# FPGA_power_v3.net
KiCad netlist of a schematic drawn in Altium Designer
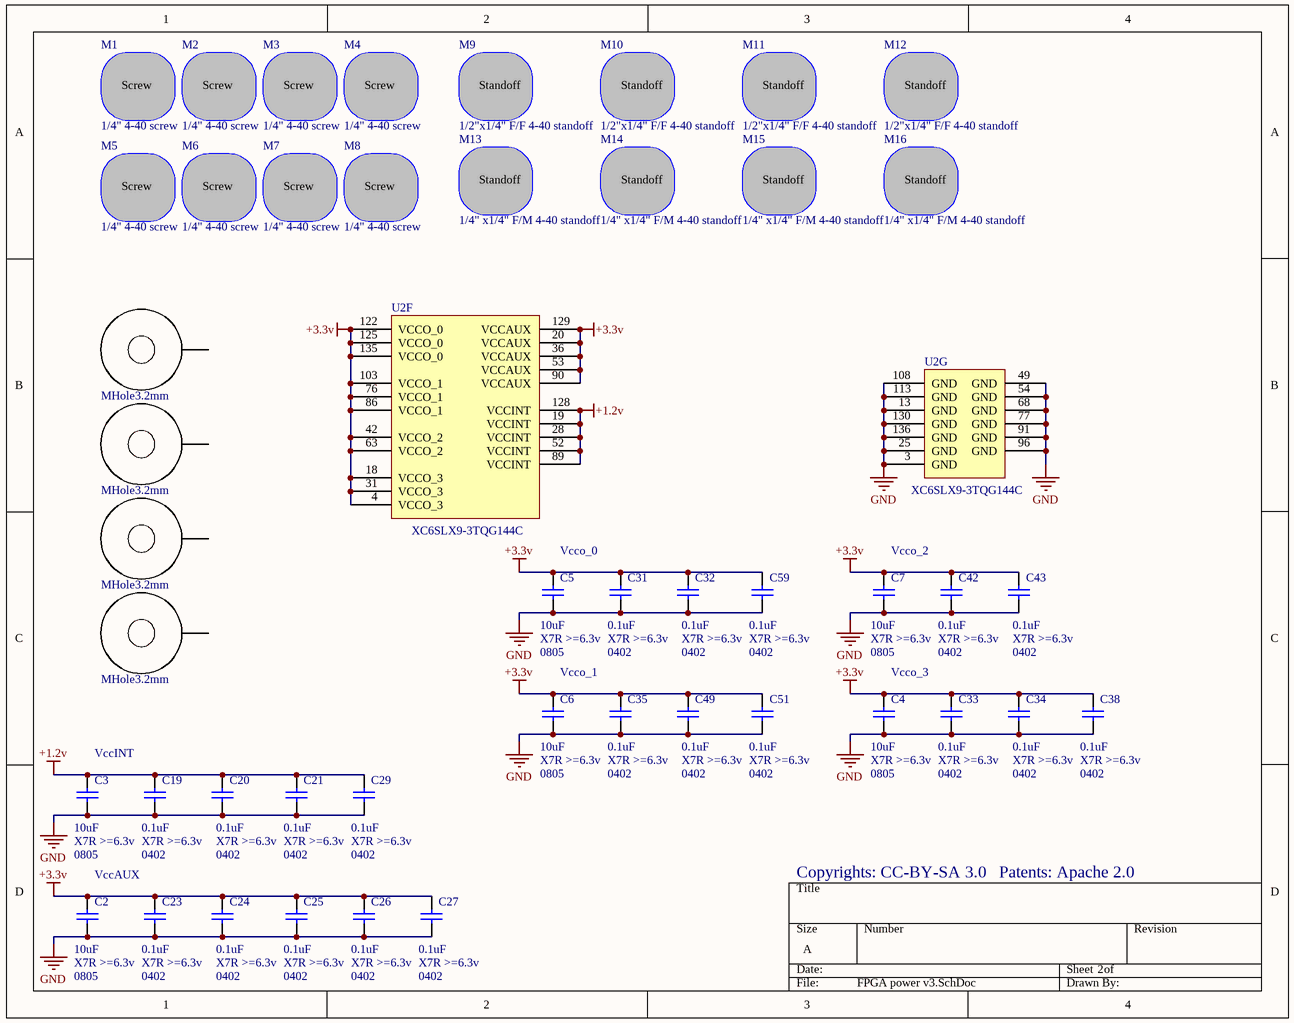
[diagram p0: FPGA power v3.SchDoc]

(export (version "E")
  (design (tool "Eeschema 10.0.6"))
  (components
    (comp (ref "C2")
      (value "10uF")
      (footprint "CAPC2012N")
      (description "CAP CER 0.1UF 25V 10% X5R 0603")
      (fields
        (field (name "PACKAGEREFERENCE") "0805")
        (field (name "TOLERANCE") "±10%")
        (field (name "RATING") "X7R >=6.3v")
      )
      (libsource (lib "Miscellaneous Devices") (part "Cap Semi"))
    )
    (comp (ref "C3")
      (value "10uF")
      (footprint "CAPC2012N")
      (description "CAP CER 0.1UF 25V 10% X5R 0603")
      (fields
        (field (name "PACKAGEREFERENCE") "0805")
        (field (name "TOLERANCE") "±10%")
        (field (name "RATING") "X7R >=6.3v")
      )
      (libsource (lib "Miscellaneous Devices") (part "Cap Semi"))
    )
    (comp (ref "C4")
      (value "10uF")
      (footprint "CAPC2012N")
      (description "CAP CER 0.1UF 25V 10% X5R 0603")
      (fields
        (field (name "PACKAGEREFERENCE") "0805")
        (field (name "TOLERANCE") "±10%")
        (field (name "RATING") "X7R >=6.3v")
      )
      (libsource (lib "Miscellaneous Devices") (part "Cap Semi"))
    )
    (comp (ref "C5")
      (value "10uF")
      (footprint "CAPC2012N")
      (description "CAP CER 0.1UF 25V 10% X5R 0603")
      (fields
        (field (name "PACKAGEREFERENCE") "0805")
        (field (name "TOLERANCE") "±10%")
        (field (name "RATING") "X7R >=6.3v")
      )
      (libsource (lib "Miscellaneous Devices") (part "Cap Semi"))
    )
    (comp (ref "C6")
      (value "10uF")
      (footprint "CAPC2012N")
      (description "CAP CER 0.1UF 25V 10% X5R 0603")
      (fields
        (field (name "PACKAGEREFERENCE") "0805")
        (field (name "TOLERANCE") "±10%")
        (field (name "RATING") "X7R >=6.3v")
      )
      (libsource (lib "Miscellaneous Devices") (part "Cap Semi"))
    )
    (comp (ref "C7")
      (value "10uF")
      (footprint "CAPC2012N")
      (description "CAP CER 0.1UF 25V 10% X5R 0603")
      (fields
        (field (name "PACKAGEREFERENCE") "0805")
        (field (name "TOLERANCE") "±10%")
        (field (name "RATING") "X7R >=6.3v")
      )
      (libsource (lib "Miscellaneous Devices") (part "Cap Semi"))
    )
    (comp (ref "C19")
      (value "0.1uF")
      (footprint "CAPC1005N")
      (description "CAP CER 0.1UF 25V 10% X5R 0603")
      (fields
        (field (name "PACKAGEREFERENCE") "0402")
        (field (name "TOLERANCE") "±10%")
        (field (name "RATING") "X7R >=6.3v")
      )
      (libsource (lib "Miscellaneous Devices") (part "Cap Semi"))
    )
    (comp (ref "C20")
      (value "0.1uF")
      (footprint "CAPC1005N")
      (description "CAP CER 0.1UF 25V 10% X5R 0603")
      (fields
        (field (name "PACKAGEREFERENCE") "0402")
        (field (name "TOLERANCE") "±10%")
        (field (name "RATING") "X7R >=6.3v")
      )
      (libsource (lib "Miscellaneous Devices") (part "Cap Semi"))
    )
    (comp (ref "C21")
      (value "0.1uF")
      (footprint "CAPC1005N")
      (description "CAP CER 0.1UF 25V 10% X5R 0603")
      (fields
        (field (name "PACKAGEREFERENCE") "0402")
        (field (name "TOLERANCE") "±10%")
        (field (name "RATING") "X7R >=6.3v")
      )
      (libsource (lib "Miscellaneous Devices") (part "Cap Semi"))
    )
    (comp (ref "C23")
      (value "0.1uF")
      (footprint "CAPC1005N")
      (description "CAP CER 0.1UF 25V 10% X5R 0603")
      (fields
        (field (name "PACKAGEREFERENCE") "0402")
        (field (name "TOLERANCE") "±10%")
        (field (name "RATING") "X7R >=6.3v")
      )
      (libsource (lib "Miscellaneous Devices") (part "Cap Semi"))
    )
    (comp (ref "C24")
      (value "0.1uF")
      (footprint "CAPC1005N")
      (description "CAP CER 0.1UF 25V 10% X5R 0603")
      (fields
        (field (name "PACKAGEREFERENCE") "0402")
        (field (name "TOLERANCE") "±10%")
        (field (name "RATING") "X7R >=6.3v")
      )
      (libsource (lib "Miscellaneous Devices") (part "Cap Semi"))
    )
    (comp (ref "C25")
      (value "0.1uF")
      (footprint "CAPC1005N")
      (description "CAP CER 0.1UF 25V 10% X5R 0603")
      (fields
        (field (name "PACKAGEREFERENCE") "0402")
        (field (name "TOLERANCE") "±10%")
        (field (name "RATING") "X7R >=6.3v")
      )
      (libsource (lib "Miscellaneous Devices") (part "Cap Semi"))
    )
    (comp (ref "C26")
      (value "0.1uF")
      (footprint "CAPC1005N")
      (description "CAP CER 0.1UF 25V 10% X5R 0603")
      (fields
        (field (name "PACKAGEREFERENCE") "0402")
        (field (name "TOLERANCE") "±10%")
        (field (name "RATING") "X7R >=6.3v")
      )
      (libsource (lib "Miscellaneous Devices") (part "Cap Semi"))
    )
    (comp (ref "C27")
      (value "0.1uF")
      (footprint "CAPC1005N")
      (description "CAP CER 0.1UF 25V 10% X5R 0603")
      (fields
        (field (name "PACKAGEREFERENCE") "0402")
        (field (name "TOLERANCE") "±10%")
        (field (name "RATING") "X7R >=6.3v")
      )
      (libsource (lib "Miscellaneous Devices") (part "Cap Semi"))
    )
    (comp (ref "C29")
      (value "0.1uF")
      (footprint "CAPC1005N")
      (description "CAP CER 0.1UF 25V 10% X5R 0603")
      (fields
        (field (name "PACKAGEREFERENCE") "0402")
        (field (name "TOLERANCE") "±10%")
        (field (name "RATING") "X7R >=6.3v")
      )
      (libsource (lib "Miscellaneous Devices") (part "Cap Semi"))
    )
    (comp (ref "C31")
      (value "0.1uF")
      (footprint "CAPC1005N")
      (description "CAP CER 0.1UF 25V 10% X5R 0603")
      (fields
        (field (name "PACKAGEREFERENCE") "0402")
        (field (name "TOLERANCE") "±10%")
        (field (name "RATING") "X7R >=6.3v")
      )
      (libsource (lib "Miscellaneous Devices") (part "Cap Semi"))
    )
    (comp (ref "C32")
      (value "0.1uF")
      (footprint "CAPC1005N")
      (description "CAP CER 0.1UF 25V 10% X5R 0603")
      (fields
        (field (name "PACKAGEREFERENCE") "0402")
        (field (name "TOLERANCE") "±10%")
        (field (name "RATING") "X7R >=6.3v")
      )
      (libsource (lib "Miscellaneous Devices") (part "Cap Semi"))
    )
    (comp (ref "C33")
      (value "0.1uF")
      (footprint "CAPC1005N")
      (description "CAP CER 0.1UF 25V 10% X5R 0603")
      (fields
        (field (name "PACKAGEREFERENCE") "0402")
        (field (name "TOLERANCE") "±10%")
        (field (name "RATING") "X7R >=6.3v")
      )
      (libsource (lib "Miscellaneous Devices") (part "Cap Semi"))
    )
    (comp (ref "C34")
      (value "0.1uF")
      (footprint "CAPC1005N")
      (description "CAP CER 0.1UF 25V 10% X5R 0603")
      (fields
        (field (name "PACKAGEREFERENCE") "0402")
        (field (name "TOLERANCE") "±10%")
        (field (name "RATING") "X7R >=6.3v")
      )
      (libsource (lib "Miscellaneous Devices") (part "Cap Semi"))
    )
    (comp (ref "C35")
      (value "0.1uF")
      (footprint "CAPC1005N")
      (description "CAP CER 0.1UF 25V 10% X5R 0603")
      (fields
        (field (name "PACKAGEREFERENCE") "0402")
        (field (name "TOLERANCE") "±10%")
        (field (name "RATING") "X7R >=6.3v")
      )
      (libsource (lib "Miscellaneous Devices") (part "Cap Semi"))
    )
    (comp (ref "C38")
      (value "0.1uF")
      (footprint "CAPC1005N")
      (description "CAP CER 0.1UF 25V 10% X5R 0603")
      (fields
        (field (name "PACKAGEREFERENCE") "0402")
        (field (name "TOLERANCE") "±10%")
        (field (name "RATING") "X7R >=6.3v")
      )
      (libsource (lib "Miscellaneous Devices") (part "Cap Semi"))
    )
    (comp (ref "C42")
      (value "0.1uF")
      (footprint "CAPC1005N")
      (description "CAP CER 0.1UF 25V 10% X5R 0603")
      (fields
        (field (name "PACKAGEREFERENCE") "0402")
        (field (name "TOLERANCE") "±10%")
        (field (name "RATING") "X7R >=6.3v")
      )
      (libsource (lib "Miscellaneous Devices") (part "Cap Semi"))
    )
    (comp (ref "C43")
      (value "0.1uF")
      (footprint "CAPC1005N")
      (description "CAP CER 0.1UF 25V 10% X5R 0603")
      (fields
        (field (name "PACKAGEREFERENCE") "0402")
        (field (name "TOLERANCE") "±10%")
        (field (name "RATING") "X7R >=6.3v")
      )
      (libsource (lib "Miscellaneous Devices") (part "Cap Semi"))
    )
    (comp (ref "C49")
      (value "0.1uF")
      (footprint "CAPC1005N")
      (description "CAP CER 0.1UF 25V 10% X5R 0603")
      (fields
        (field (name "PACKAGEREFERENCE") "0402")
        (field (name "TOLERANCE") "±10%")
        (field (name "RATING") "X7R >=6.3v")
      )
      (libsource (lib "Miscellaneous Devices") (part "Cap Semi"))
    )
    (comp (ref "C51")
      (value "0.1uF")
      (footprint "CAPC1005N")
      (description "CAP CER 0.1UF 25V 10% X5R 0603")
      (fields
        (field (name "PACKAGEREFERENCE") "0402")
        (field (name "TOLERANCE") "±10%")
        (field (name "RATING") "X7R >=6.3v")
      )
      (libsource (lib "Miscellaneous Devices") (part "Cap Semi"))
    )
    (comp (ref "C59")
      (value "0.1uF")
      (footprint "CAPC1005N")
      (description "CAP CER 0.1UF 25V 10% X5R 0603")
      (fields
        (field (name "PACKAGEREFERENCE") "0402")
        (field (name "TOLERANCE") "±10%")
        (field (name "RATING") "X7R >=6.3v")
      )
      (libsource (lib "Miscellaneous Devices") (part "Cap Semi"))
    )
    (comp (ref "H1") (value "MHole3.2mm") (footprint "mounting hole") (libsource (lib "dbww") (part "MHole")))
    (comp (ref "H2") (value "MHole3.2mm") (footprint "mounting hole") (libsource (lib "dbww") (part "MHole")))
    (comp (ref "H3") (value "MHole3.2mm") (footprint "mounting hole") (libsource (lib "dbww") (part "MHole")))
    (comp (ref "H4") (value "MHole3.2mm") (footprint "mounting hole") (libsource (lib "dbww") (part "MHole")))
    (comp (ref "M1")
      (value "1/4\" 4-40 screw")
      (footprint "fiducial")
      (libsource (lib "OpenVizsla symbols") (part "Screw"))
    )
    (comp (ref "M2")
      (value "1/4\" 4-40 screw")
      (footprint "fiducial")
      (libsource (lib "OpenVizsla symbols") (part "Screw"))
    )
    (comp (ref "M3")
      (value "1/4\" 4-40 screw")
      (footprint "fiducial")
      (libsource (lib "OpenVizsla symbols") (part "Screw"))
    )
    (comp (ref "M4")
      (value "1/4\" 4-40 screw")
      (footprint "fiducial")
      (libsource (lib "OpenVizsla symbols") (part "Screw"))
    )
    (comp (ref "M5")
      (value "1/4\" 4-40 screw")
      (footprint "fiducial")
      (libsource (lib "OpenVizsla symbols") (part "Screw"))
    )
    (comp (ref "M6")
      (value "1/4\" 4-40 screw")
      (footprint "fiducial")
      (libsource (lib "OpenVizsla symbols") (part "Screw"))
    )
    (comp (ref "M7")
      (value "1/4\" 4-40 screw")
      (footprint "fiducial")
      (libsource (lib "OpenVizsla symbols") (part "Screw"))
    )
    (comp (ref "M8")
      (value "1/4\" 4-40 screw")
      (footprint "fiducial")
      (libsource (lib "OpenVizsla symbols") (part "Screw"))
    )
    (comp (ref "M9")
      (value "1/2\"x1/4\" F/F 4-40 standoff")
      (footprint "fiducial")
      (libsource (lib "OpenVizsla symbols") (part "Standoff"))
    )
    (comp (ref "M10")
      (value "1/2\"x1/4\" F/F 4-40 standoff")
      (footprint "fiducial")
      (libsource (lib "OpenVizsla symbols") (part "Standoff"))
    )
    (comp (ref "M11")
      (value "1/2\"x1/4\" F/F 4-40 standoff")
      (footprint "fiducial")
      (libsource (lib "OpenVizsla symbols") (part "Standoff"))
    )
    (comp (ref "M12")
      (value "1/2\"x1/4\" F/F 4-40 standoff")
      (footprint "fiducial")
      (libsource (lib "OpenVizsla symbols") (part "Standoff"))
    )
    (comp (ref "M13")
      (value "1/4\" x1/4\" F/M 4-40 standoff")
      (footprint "fiducial")
      (description "1/4\"x1/4\" F/M 4-40 standof")
      (libsource (lib "OpenVizsla symbols") (part "Standoff"))
    )
    (comp (ref "M14")
      (value "1/4\" x1/4\" F/M 4-40 standoff")
      (footprint "fiducial")
      (description "1/4\"x1/4\" F/M 4-40 standof")
      (libsource (lib "OpenVizsla symbols") (part "Standoff"))
    )
    (comp (ref "M15")
      (value "1/4\" x1/4\" F/M 4-40 standoff")
      (footprint "fiducial")
      (description "1/4\"x1/4\" F/M 4-40 standof")
      (libsource (lib "OpenVizsla symbols") (part "Standoff"))
    )
    (comp (ref "M16")
      (value "1/4\" x1/4\" F/M 4-40 standoff")
      (footprint "fiducial")
      (description "1/4\"x1/4\" F/M 4-40 standof")
      (libsource (lib "OpenVizsla symbols") (part "Standoff"))
    )
    (comp (ref "U2")
      (value "XC6SLX9-3TQG144C")
      (footprint "TQG144_N")
      (libsource (lib "Xilinx Spartan-6") (part "XC6SLX9-3TQG144C"))
    )
  )
  (nets
    (net (code "1") (name "+1.2v") (class "Default")
      (node (ref "C19") (pin "2") (pinfunction "2_2") (pintype "passive"))
      (node (ref "C20") (pin "2") (pinfunction "2_2") (pintype "passive"))
      (node (ref "C21") (pin "2") (pinfunction "2_2") (pintype "passive"))
      (node (ref "C29") (pin "2") (pinfunction "2_2") (pintype "passive"))
      (node (ref "C3") (pin "2") (pinfunction "2_2") (pintype "passive"))
      (node (ref "U2") (pin "128") (pinfunction "VCCINT_128") (pintype "power_in"))
      (node (ref "U2") (pin "19") (pinfunction "VCCINT_19") (pintype "power_in"))
      (node (ref "U2") (pin "28") (pinfunction "VCCINT_28") (pintype "power_in"))
      (node (ref "U2") (pin "52") (pinfunction "VCCINT_52") (pintype "power_in"))
      (node (ref "U2") (pin "89") (pinfunction "VCCINT_89") (pintype "power_in"))
    )
    (net (code "2") (name "+3.3v") (class "Default")
      (node (ref "C2") (pin "2") (pinfunction "2_2") (pintype "passive"))
      (node (ref "C23") (pin "2") (pinfunction "2_2") (pintype "passive"))
      (node (ref "C24") (pin "2") (pinfunction "2_2") (pintype "passive"))
      (node (ref "C25") (pin "2") (pinfunction "2_2") (pintype "passive"))
      (node (ref "C26") (pin "2") (pinfunction "2_2") (pintype "passive"))
      (node (ref "C27") (pin "2") (pinfunction "2_2") (pintype "passive"))
      (node (ref "C31") (pin "2") (pinfunction "2_2") (pintype "passive"))
      (node (ref "C32") (pin "2") (pinfunction "2_2") (pintype "passive"))
      (node (ref "C33") (pin "2") (pinfunction "2_2") (pintype "passive"))
      (node (ref "C34") (pin "2") (pinfunction "2_2") (pintype "passive"))
      (node (ref "C35") (pin "2") (pinfunction "2_2") (pintype "passive"))
      (node (ref "C38") (pin "2") (pinfunction "2_2") (pintype "passive"))
      (node (ref "C4") (pin "2") (pinfunction "2_2") (pintype "passive"))
      (node (ref "C42") (pin "2") (pinfunction "2_2") (pintype "passive"))
      (node (ref "C43") (pin "2") (pinfunction "2_2") (pintype "passive"))
      (node (ref "C49") (pin "2") (pinfunction "2_2") (pintype "passive"))
      (node (ref "C5") (pin "2") (pinfunction "2_2") (pintype "passive"))
      (node (ref "C51") (pin "2") (pinfunction "2_2") (pintype "passive"))
      (node (ref "C59") (pin "2") (pinfunction "2_2") (pintype "passive"))
      (node (ref "C6") (pin "2") (pinfunction "2_2") (pintype "passive"))
      (node (ref "C7") (pin "2") (pinfunction "2_2") (pintype "passive"))
      (node (ref "U2") (pin "103") (pinfunction "VCCO_1_103") (pintype "power_in"))
      (node (ref "U2") (pin "122") (pinfunction "VCCO_0_122") (pintype "power_in"))
      (node (ref "U2") (pin "125") (pinfunction "VCCO_0_125") (pintype "power_in"))
      (node (ref "U2") (pin "129") (pinfunction "VCCAUX_129") (pintype "power_in"))
      (node (ref "U2") (pin "135") (pinfunction "VCCO_0_135") (pintype "power_in"))
      (node (ref "U2") (pin "18") (pinfunction "VCCO_3_18") (pintype "power_in"))
      (node (ref "U2") (pin "20") (pinfunction "VCCAUX_20") (pintype "power_in"))
      (node (ref "U2") (pin "31") (pinfunction "VCCO_3_31") (pintype "power_in"))
      (node (ref "U2") (pin "36") (pinfunction "VCCAUX_36") (pintype "power_in"))
      (node (ref "U2") (pin "4") (pinfunction "VCCO_3_4") (pintype "power_in"))
      (node (ref "U2") (pin "42") (pinfunction "VCCO_2_42") (pintype "power_in"))
      (node (ref "U2") (pin "53") (pinfunction "VCCAUX_53") (pintype "power_in"))
      (node (ref "U2") (pin "63") (pinfunction "VCCO_2_63") (pintype "power_in"))
      (node (ref "U2") (pin "76") (pinfunction "VCCO_1_76") (pintype "power_in"))
      (node (ref "U2") (pin "86") (pinfunction "VCCO_1_86") (pintype "power_in"))
      (node (ref "U2") (pin "90") (pinfunction "VCCAUX_90") (pintype "power_in"))
    )
    (net (code "3") (name "GND") (class "Default")
      (node (ref "C19") (pin "1") (pinfunction "1_1") (pintype "passive"))
      (node (ref "C2") (pin "1") (pinfunction "1_1") (pintype "passive"))
      (node (ref "C20") (pin "1") (pinfunction "1_1") (pintype "passive"))
      (node (ref "C21") (pin "1") (pinfunction "1_1") (pintype "passive"))
      (node (ref "C23") (pin "1") (pinfunction "1_1") (pintype "passive"))
      (node (ref "C24") (pin "1") (pinfunction "1_1") (pintype "passive"))
      (node (ref "C25") (pin "1") (pinfunction "1_1") (pintype "passive"))
      (node (ref "C26") (pin "1") (pinfunction "1_1") (pintype "passive"))
      (node (ref "C27") (pin "1") (pinfunction "1_1") (pintype "passive"))
      (node (ref "C29") (pin "1") (pinfunction "1_1") (pintype "passive"))
      (node (ref "C3") (pin "1") (pinfunction "1_1") (pintype "passive"))
      (node (ref "C31") (pin "1") (pinfunction "1_1") (pintype "passive"))
      (node (ref "C32") (pin "1") (pinfunction "1_1") (pintype "passive"))
      (node (ref "C33") (pin "1") (pinfunction "1_1") (pintype "passive"))
      (node (ref "C34") (pin "1") (pinfunction "1_1") (pintype "passive"))
      (node (ref "C35") (pin "1") (pinfunction "1_1") (pintype "passive"))
      (node (ref "C38") (pin "1") (pinfunction "1_1") (pintype "passive"))
      (node (ref "C4") (pin "1") (pinfunction "1_1") (pintype "passive"))
      (node (ref "C42") (pin "1") (pinfunction "1_1") (pintype "passive"))
      (node (ref "C43") (pin "1") (pinfunction "1_1") (pintype "passive"))
      (node (ref "C49") (pin "1") (pinfunction "1_1") (pintype "passive"))
      (node (ref "C5") (pin "1") (pinfunction "1_1") (pintype "passive"))
      (node (ref "C51") (pin "1") (pinfunction "1_1") (pintype "passive"))
      (node (ref "C59") (pin "1") (pinfunction "1_1") (pintype "passive"))
      (node (ref "C6") (pin "1") (pinfunction "1_1") (pintype "passive"))
      (node (ref "C7") (pin "1") (pinfunction "1_1") (pintype "passive"))
      (node (ref "U2") (pin "108") (pinfunction "GND_108") (pintype "power_in"))
      (node (ref "U2") (pin "113") (pinfunction "GND_113") (pintype "power_in"))
      (node (ref "U2") (pin "13") (pinfunction "GND_13") (pintype "power_in"))
      (node (ref "U2") (pin "130") (pinfunction "GND_130") (pintype "power_in"))
      (node (ref "U2") (pin "136") (pinfunction "GND_136") (pintype "power_in"))
      (node (ref "U2") (pin "25") (pinfunction "GND_25") (pintype "power_in"))
      (node (ref "U2") (pin "3") (pinfunction "GND_3") (pintype "power_in"))
      (node (ref "U2") (pin "49") (pinfunction "GND_49") (pintype "power_in"))
      (node (ref "U2") (pin "54") (pinfunction "GND_54") (pintype "power_in"))
      (node (ref "U2") (pin "68") (pinfunction "GND_68") (pintype "power_in"))
      (node (ref "U2") (pin "77") (pinfunction "GND_77") (pintype "power_in"))
      (node (ref "U2") (pin "91") (pinfunction "GND_91") (pintype "power_in"))
      (node (ref "U2") (pin "96") (pinfunction "GND_96") (pintype "power_in"))
    )
    (net (code "4") (name "unconnected-(H1-Pad1)") (class "Default")
      (node (ref "H1") (pin "1") (pinfunction "1_1") (pintype "passive"))
    )
    (net (code "5") (name "unconnected-(H2-Pad1)") (class "Default")
      (node (ref "H2") (pin "1") (pinfunction "1_1") (pintype "passive"))
    )
    (net (code "6") (name "unconnected-(H3-Pad1)") (class "Default")
      (node (ref "H3") (pin "1") (pinfunction "1_1") (pintype "passive"))
    )
    (net (code "7") (name "unconnected-(H4-Pad1)") (class "Default")
      (node (ref "H4") (pin "1") (pinfunction "1_1") (pintype "passive"))
    )
  )
)
